# SolenoidDriverCircuit.net
KiCad netlist of a schematic drawn in EAGLE
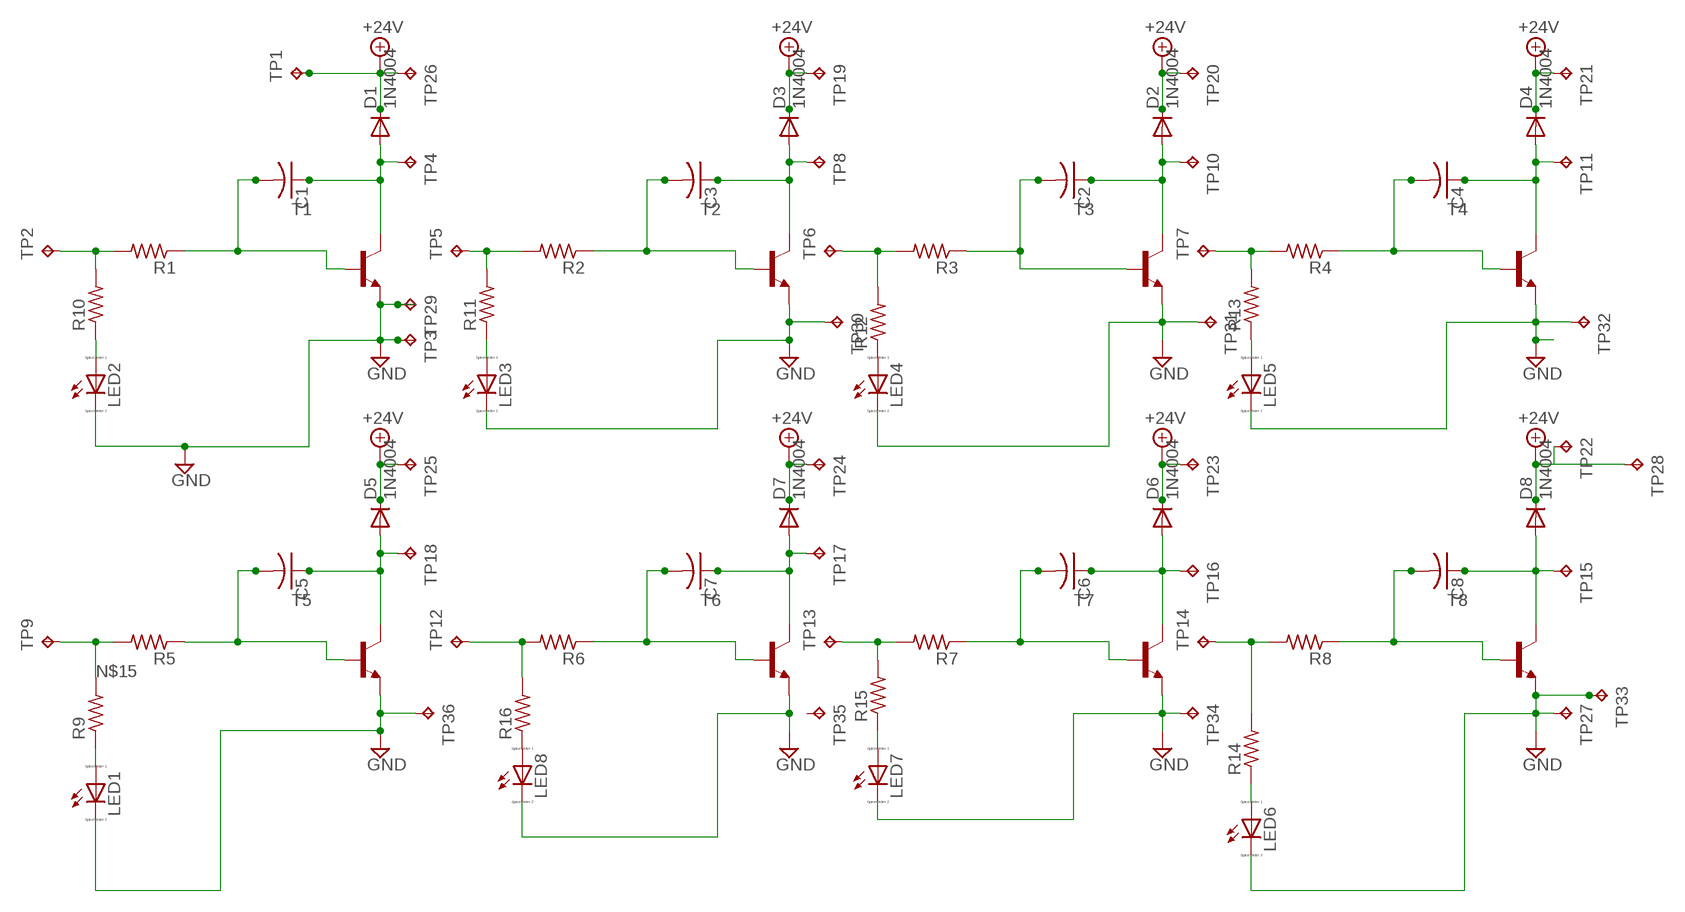
[diagram p0: schematic, sheet 1]

(export (version "E")
  (design (tool "Eeschema 10.0.6"))
  (components
    (comp (ref "C1")
      (value "C-US050-024X044")
      (footprint "eagle-import:C050-024X044")
      (libsource (lib "eagle-import") (part "C-US050-024X044"))
    )
    (comp (ref "C2")
      (value "C-US050-024X044")
      (footprint "eagle-import:C050-024X044")
      (libsource (lib "eagle-import") (part "C-US050-024X044"))
    )
    (comp (ref "C3")
      (value "C-US050-024X044")
      (footprint "eagle-import:C050-024X044")
      (libsource (lib "eagle-import") (part "C-US050-024X044"))
    )
    (comp (ref "C4")
      (value "C-US050-024X044")
      (footprint "eagle-import:C050-024X044")
      (libsource (lib "eagle-import") (part "C-US050-024X044"))
    )
    (comp (ref "C5")
      (value "C-US050-024X044")
      (footprint "eagle-import:C050-024X044")
      (libsource (lib "eagle-import") (part "C-US050-024X044"))
    )
    (comp (ref "C6")
      (value "C-US050-024X044")
      (footprint "eagle-import:C050-024X044")
      (libsource (lib "eagle-import") (part "C-US050-024X044"))
    )
    (comp (ref "C7")
      (value "C-US050-024X044")
      (footprint "eagle-import:C050-024X044")
      (libsource (lib "eagle-import") (part "C-US050-024X044"))
    )
    (comp (ref "C8")
      (value "C-US050-024X044")
      (footprint "eagle-import:C050-024X044")
      (libsource (lib "eagle-import") (part "C-US050-024X044"))
    )
    (comp (ref "D1")
      (value "1N4004")
      (footprint "eagle-import:DO41-10")
      (libsource (lib "eagle-import") (part "1N4004"))
    )
    (comp (ref "D2")
      (value "1N4004")
      (footprint "eagle-import:DO41-10")
      (libsource (lib "eagle-import") (part "1N4004"))
    )
    (comp (ref "D3")
      (value "1N4004")
      (footprint "eagle-import:DO41-10")
      (libsource (lib "eagle-import") (part "1N4004"))
    )
    (comp (ref "D4")
      (value "1N4004")
      (footprint "eagle-import:DO41-10")
      (libsource (lib "eagle-import") (part "1N4004"))
    )
    (comp (ref "D5")
      (value "1N4004")
      (footprint "eagle-import:DO41-10")
      (libsource (lib "eagle-import") (part "1N4004"))
    )
    (comp (ref "D6")
      (value "1N4004")
      (footprint "eagle-import:DO41-10")
      (libsource (lib "eagle-import") (part "1N4004"))
    )
    (comp (ref "D7")
      (value "1N4004")
      (footprint "eagle-import:DO41-10")
      (libsource (lib "eagle-import") (part "1N4004"))
    )
    (comp (ref "D8")
      (value "1N4004")
      (footprint "eagle-import:DO41-10")
      (libsource (lib "eagle-import") (part "1N4004"))
    )
    (comp (ref "LED1")
      (value "LED_ELD260")
      (footprint "eagle-import:LED_LD260")
      (libsource (lib "eagle-import") (part "LED_ELD260"))
    )
    (comp (ref "LED2")
      (value "LED_ELD260")
      (footprint "eagle-import:LED_LD260")
      (libsource (lib "eagle-import") (part "LED_ELD260"))
    )
    (comp (ref "LED3")
      (value "LED_ELD260")
      (footprint "eagle-import:LED_LD260")
      (libsource (lib "eagle-import") (part "LED_ELD260"))
    )
    (comp (ref "LED4")
      (value "LED_ELD260")
      (footprint "eagle-import:LED_LD260")
      (libsource (lib "eagle-import") (part "LED_ELD260"))
    )
    (comp (ref "LED5")
      (value "LED_ELD260")
      (footprint "eagle-import:LED_LD260")
      (libsource (lib "eagle-import") (part "LED_ELD260"))
    )
    (comp (ref "LED6")
      (value "LED_ELD260")
      (footprint "eagle-import:LED_LD260")
      (libsource (lib "eagle-import") (part "LED_ELD260"))
    )
    (comp (ref "LED7")
      (value "LED_ELD260")
      (footprint "eagle-import:LED_LD260")
      (libsource (lib "eagle-import") (part "LED_ELD260"))
    )
    (comp (ref "LED8")
      (value "LED_ELD260")
      (footprint "eagle-import:LED_LD260")
      (libsource (lib "eagle-import") (part "LED_ELD260"))
    )
    (comp (ref "R1")
      (value "R-US_0207/2V")
      (footprint "eagle-import:0207_2V")
      (libsource (lib "eagle-import") (part "R-US_0207/2V"))
    )
    (comp (ref "R2")
      (value "R-US_0207/2V")
      (footprint "eagle-import:0207_2V")
      (libsource (lib "eagle-import") (part "R-US_0207/2V"))
    )
    (comp (ref "R3")
      (value "R-US_0207/2V")
      (footprint "eagle-import:0207_2V")
      (libsource (lib "eagle-import") (part "R-US_0207/2V"))
    )
    (comp (ref "R4")
      (value "R-US_0207/2V")
      (footprint "eagle-import:0207_2V")
      (libsource (lib "eagle-import") (part "R-US_0207/2V"))
    )
    (comp (ref "R5")
      (value "R-US_0207/2V")
      (footprint "eagle-import:0207_2V")
      (libsource (lib "eagle-import") (part "R-US_0207/2V"))
    )
    (comp (ref "R6")
      (value "R-US_0207/2V")
      (footprint "eagle-import:0207_2V")
      (libsource (lib "eagle-import") (part "R-US_0207/2V"))
    )
    (comp (ref "R7")
      (value "R-US_0207/2V")
      (footprint "eagle-import:0207_2V")
      (libsource (lib "eagle-import") (part "R-US_0207/2V"))
    )
    (comp (ref "R8")
      (value "R-US_0207/2V")
      (footprint "eagle-import:0207_2V")
      (libsource (lib "eagle-import") (part "R-US_0207/2V"))
    )
    (comp (ref "R9")
      (value "R-US_0207/2V")
      (footprint "eagle-import:0207_2V")
      (libsource (lib "eagle-import") (part "R-US_0207/2V"))
    )
    (comp (ref "R10")
      (value "R-US_0207/2V")
      (footprint "eagle-import:0207_2V")
      (libsource (lib "eagle-import") (part "R-US_0207/2V"))
    )
    (comp (ref "R11")
      (value "R-US_0207/2V")
      (footprint "eagle-import:0207_2V")
      (libsource (lib "eagle-import") (part "R-US_0207/2V"))
    )
    (comp (ref "R12")
      (value "R-US_0207/2V")
      (footprint "eagle-import:0207_2V")
      (libsource (lib "eagle-import") (part "R-US_0207/2V"))
    )
    (comp (ref "R13")
      (value "R-US_0207/2V")
      (footprint "eagle-import:0207_2V")
      (libsource (lib "eagle-import") (part "R-US_0207/2V"))
    )
    (comp (ref "R14")
      (value "R-US_0207/2V")
      (footprint "eagle-import:0207_2V")
      (libsource (lib "eagle-import") (part "R-US_0207/2V"))
    )
    (comp (ref "R15")
      (value "R-US_0207/2V")
      (footprint "eagle-import:0207_2V")
      (libsource (lib "eagle-import") (part "R-US_0207/2V"))
    )
    (comp (ref "R16")
      (value "R-US_0207/2V")
      (footprint "eagle-import:0207_2V")
      (libsource (lib "eagle-import") (part "R-US_0207/2V"))
    )
    (comp (ref "T1")
      (value "-NPN-TO220V")
      (footprint "eagle-import:TO220V")
      (libsource (lib "eagle-import") (part "-NPN-TO220V"))
    )
    (comp (ref "T2")
      (value "-NPN-TO220V")
      (footprint "eagle-import:TO220V")
      (libsource (lib "eagle-import") (part "-NPN-TO220V"))
    )
    (comp (ref "T3")
      (value "-NPN-TO220V")
      (footprint "eagle-import:TO220V")
      (libsource (lib "eagle-import") (part "-NPN-TO220V"))
    )
    (comp (ref "T4")
      (value "-NPN-TO220V")
      (footprint "eagle-import:TO220V")
      (libsource (lib "eagle-import") (part "-NPN-TO220V"))
    )
    (comp (ref "T5")
      (value "-NPN-TO220V")
      (footprint "eagle-import:TO220V")
      (libsource (lib "eagle-import") (part "-NPN-TO220V"))
    )
    (comp (ref "T6")
      (value "-NPN-TO220V")
      (footprint "eagle-import:TO220V")
      (libsource (lib "eagle-import") (part "-NPN-TO220V"))
    )
    (comp (ref "T7")
      (value "-NPN-TO220V")
      (footprint "eagle-import:TO220V")
      (libsource (lib "eagle-import") (part "-NPN-TO220V"))
    )
    (comp (ref "T8")
      (value "-NPN-TO220V")
      (footprint "eagle-import:TO220V")
      (libsource (lib "eagle-import") (part "-NPN-TO220V"))
    )
    (comp (ref "TP1")
      (value "TPPAD1-13Y")
      (footprint "eagle-import:P1-13Y")
      (libsource (lib "eagle-import") (part "TPPAD1-13Y"))
    )
    (comp (ref "TP2")
      (value "TPPAD1-13")
      (footprint "eagle-import:P1-13")
      (libsource (lib "eagle-import") (part "TPPAD1-13"))
    )
    (comp (ref "TP3")
      (value "TPPAD1-13Y")
      (footprint "eagle-import:P1-13Y")
      (libsource (lib "eagle-import") (part "TPPAD1-13Y"))
    )
    (comp (ref "TP4")
      (value "TPPAD1-13Y")
      (footprint "eagle-import:P1-13Y")
      (libsource (lib "eagle-import") (part "TPPAD1-13Y"))
    )
    (comp (ref "TP5")
      (value "TPPAD1-13")
      (footprint "eagle-import:P1-13")
      (libsource (lib "eagle-import") (part "TPPAD1-13"))
    )
    (comp (ref "TP6")
      (value "TPPAD1-13")
      (footprint "eagle-import:P1-13")
      (libsource (lib "eagle-import") (part "TPPAD1-13"))
    )
    (comp (ref "TP7")
      (value "TPPAD1-13")
      (footprint "eagle-import:P1-13")
      (libsource (lib "eagle-import") (part "TPPAD1-13"))
    )
    (comp (ref "TP8")
      (value "TPPAD1-13Y")
      (footprint "eagle-import:P1-13Y")
      (libsource (lib "eagle-import") (part "TPPAD1-13Y"))
    )
    (comp (ref "TP9")
      (value "TPPAD1-13")
      (footprint "eagle-import:P1-13")
      (libsource (lib "eagle-import") (part "TPPAD1-13"))
    )
    (comp (ref "TP10")
      (value "TPPAD1-13Y")
      (footprint "eagle-import:P1-13Y")
      (libsource (lib "eagle-import") (part "TPPAD1-13Y"))
    )
    (comp (ref "TP11")
      (value "TPPAD1-13Y")
      (footprint "eagle-import:P1-13Y")
      (libsource (lib "eagle-import") (part "TPPAD1-13Y"))
    )
    (comp (ref "TP12")
      (value "TPPAD1-13")
      (footprint "eagle-import:P1-13")
      (libsource (lib "eagle-import") (part "TPPAD1-13"))
    )
    (comp (ref "TP13")
      (value "TPPAD1-13")
      (footprint "eagle-import:P1-13")
      (libsource (lib "eagle-import") (part "TPPAD1-13"))
    )
    (comp (ref "TP14")
      (value "TPPAD1-13")
      (footprint "eagle-import:P1-13")
      (libsource (lib "eagle-import") (part "TPPAD1-13"))
    )
    (comp (ref "TP15")
      (value "TPPAD1-13Y")
      (footprint "eagle-import:P1-13Y")
      (libsource (lib "eagle-import") (part "TPPAD1-13Y"))
    )
    (comp (ref "TP16")
      (value "TPPAD1-13Y")
      (footprint "eagle-import:P1-13Y")
      (libsource (lib "eagle-import") (part "TPPAD1-13Y"))
    )
    (comp (ref "TP17")
      (value "TPPAD1-13Y")
      (footprint "eagle-import:P1-13Y")
      (libsource (lib "eagle-import") (part "TPPAD1-13Y"))
    )
    (comp (ref "TP18")
      (value "TPPAD1-13Y")
      (footprint "eagle-import:P1-13Y")
      (libsource (lib "eagle-import") (part "TPPAD1-13Y"))
    )
    (comp (ref "TP19")
      (value "TPPAD1-13Y")
      (footprint "eagle-import:P1-13Y")
      (libsource (lib "eagle-import") (part "TPPAD1-13Y"))
    )
    (comp (ref "TP20")
      (value "TPPAD1-13Y")
      (footprint "eagle-import:P1-13Y")
      (libsource (lib "eagle-import") (part "TPPAD1-13Y"))
    )
    (comp (ref "TP21")
      (value "TPPAD1-13Y")
      (footprint "eagle-import:P1-13Y")
      (libsource (lib "eagle-import") (part "TPPAD1-13Y"))
    )
    (comp (ref "TP22")
      (value "TPPAD1-13Y")
      (footprint "eagle-import:P1-13Y")
      (libsource (lib "eagle-import") (part "TPPAD1-13Y"))
    )
    (comp (ref "TP23")
      (value "TPPAD1-13Y")
      (footprint "eagle-import:P1-13Y")
      (libsource (lib "eagle-import") (part "TPPAD1-13Y"))
    )
    (comp (ref "TP24")
      (value "TPPAD1-13Y")
      (footprint "eagle-import:P1-13Y")
      (libsource (lib "eagle-import") (part "TPPAD1-13Y"))
    )
    (comp (ref "TP25")
      (value "TPPAD1-13Y")
      (footprint "eagle-import:P1-13Y")
      (libsource (lib "eagle-import") (part "TPPAD1-13Y"))
    )
    (comp (ref "TP26")
      (value "TPPAD1-13Y")
      (footprint "eagle-import:P1-13Y")
      (libsource (lib "eagle-import") (part "TPPAD1-13Y"))
    )
    (comp (ref "TP27")
      (value "TPPAD1-13Y")
      (footprint "eagle-import:P1-13Y")
      (libsource (lib "eagle-import") (part "TPPAD1-13Y"))
    )
    (comp (ref "TP28")
      (value "TPPAD1-13Y")
      (footprint "eagle-import:P1-13Y")
      (libsource (lib "eagle-import") (part "TPPAD1-13Y"))
    )
    (comp (ref "TP29")
      (value "TPPAD1-13")
      (footprint "eagle-import:P1-13")
      (libsource (lib "eagle-import") (part "TPPAD1-13"))
    )
    (comp (ref "TP30")
      (value "TPPAD1-13")
      (footprint "eagle-import:P1-13")
      (libsource (lib "eagle-import") (part "TPPAD1-13"))
    )
    (comp (ref "TP31")
      (value "TPPAD1-13")
      (footprint "eagle-import:P1-13")
      (libsource (lib "eagle-import") (part "TPPAD1-13"))
    )
    (comp (ref "TP32")
      (value "TPPAD1-13")
      (footprint "eagle-import:P1-13")
      (libsource (lib "eagle-import") (part "TPPAD1-13"))
    )
    (comp (ref "TP33")
      (value "TPPAD1-13")
      (footprint "eagle-import:P1-13")
      (libsource (lib "eagle-import") (part "TPPAD1-13"))
    )
    (comp (ref "TP34")
      (value "TPPAD1-13")
      (footprint "eagle-import:P1-13")
      (libsource (lib "eagle-import") (part "TPPAD1-13"))
    )
    (comp (ref "TP35")
      (value "TPPAD1-13")
      (footprint "eagle-import:P1-13")
      (libsource (lib "eagle-import") (part "TPPAD1-13"))
    )
    (comp (ref "TP36")
      (value "TPPAD1-13")
      (footprint "eagle-import:P1-13")
      (libsource (lib "eagle-import") (part "TPPAD1-13"))
    )
  )
  (nets
    (net (code "1") (name "+24V") (class "Default")
      (node (ref "D1") (pin "C") (pinfunction "C_C") (pintype "passive"))
      (node (ref "D2") (pin "C") (pinfunction "C_C") (pintype "passive"))
      (node (ref "D3") (pin "C") (pinfunction "C_C") (pintype "passive"))
      (node (ref "D4") (pin "C") (pinfunction "C_C") (pintype "passive"))
      (node (ref "D5") (pin "C") (pinfunction "C_C") (pintype "passive"))
      (node (ref "D6") (pin "C") (pinfunction "C_C") (pintype "passive"))
      (node (ref "D7") (pin "C") (pinfunction "C_C") (pintype "passive"))
      (node (ref "D8") (pin "C") (pinfunction "C_C") (pintype "passive"))
      (node (ref "TP1") (pin "TP") (pinfunction "TP_TP") (pintype "input"))
      (node (ref "TP19") (pin "TP") (pinfunction "TP_TP") (pintype "input"))
      (node (ref "TP20") (pin "TP") (pinfunction "TP_TP") (pintype "input"))
      (node (ref "TP21") (pin "TP") (pinfunction "TP_TP") (pintype "input"))
      (node (ref "TP22") (pin "TP") (pinfunction "TP_TP") (pintype "input"))
      (node (ref "TP23") (pin "TP") (pinfunction "TP_TP") (pintype "input"))
      (node (ref "TP24") (pin "TP") (pinfunction "TP_TP") (pintype "input"))
      (node (ref "TP25") (pin "TP") (pinfunction "TP_TP") (pintype "input"))
      (node (ref "TP26") (pin "TP") (pinfunction "TP_TP") (pintype "input"))
      (node (ref "TP28") (pin "TP") (pinfunction "TP_TP") (pintype "input"))
    )
    (net (code "2") (name "/N$15") (class "Default")
      (node (ref "R5") (pin "2") (pinfunction "2_2") (pintype "passive"))
      (node (ref "R9") (pin "2") (pinfunction "2_2") (pintype "passive"))
      (node (ref "TP9") (pin "TP") (pinfunction "TP_TP") (pintype "input"))
    )
    (net (code "3") (name "GND") (class "Default")
      (node (ref "LED1") (pin "K") (pinfunction "C_K") (pintype "passive"))
      (node (ref "LED2") (pin "K") (pinfunction "C_K") (pintype "passive"))
      (node (ref "LED3") (pin "K") (pinfunction "C_K") (pintype "passive"))
      (node (ref "LED4") (pin "K") (pinfunction "C_K") (pintype "passive"))
      (node (ref "LED5") (pin "K") (pinfunction "C_K") (pintype "passive"))
      (node (ref "LED6") (pin "K") (pinfunction "C_K") (pintype "passive"))
      (node (ref "LED7") (pin "K") (pinfunction "C_K") (pintype "passive"))
      (node (ref "LED8") (pin "K") (pinfunction "C_K") (pintype "passive"))
      (node (ref "T1") (pin "3") (pinfunction "E_3") (pintype "passive"))
      (node (ref "T2") (pin "3") (pinfunction "E_3") (pintype "passive"))
      (node (ref "T3") (pin "3") (pinfunction "E_3") (pintype "passive"))
      (node (ref "T4") (pin "3") (pinfunction "E_3") (pintype "passive"))
      (node (ref "T5") (pin "3") (pinfunction "E_3") (pintype "passive"))
      (node (ref "T6") (pin "3") (pinfunction "E_3") (pintype "passive"))
      (node (ref "T7") (pin "3") (pinfunction "E_3") (pintype "passive"))
      (node (ref "T8") (pin "3") (pinfunction "E_3") (pintype "passive"))
      (node (ref "TP27") (pin "TP") (pinfunction "TP_TP") (pintype "input"))
      (node (ref "TP29") (pin "TP") (pinfunction "TP_TP") (pintype "input"))
      (node (ref "TP3") (pin "TP") (pinfunction "TP_TP") (pintype "input"))
      (node (ref "TP30") (pin "TP") (pinfunction "TP_TP") (pintype "input"))
      (node (ref "TP31") (pin "TP") (pinfunction "TP_TP") (pintype "input"))
      (node (ref "TP32") (pin "TP") (pinfunction "TP_TP") (pintype "input"))
      (node (ref "TP33") (pin "TP") (pinfunction "TP_TP") (pintype "input"))
      (node (ref "TP34") (pin "TP") (pinfunction "TP_TP") (pintype "input"))
      (node (ref "TP36") (pin "TP") (pinfunction "TP_TP") (pintype "input"))
    )
    (net (code "4") (name "Net-(LED1-PadA)") (class "Default")
      (node (ref "LED1") (pin "A") (pinfunction "A_A") (pintype "passive"))
      (node (ref "R9") (pin "1") (pinfunction "1_1") (pintype "passive"))
    )
    (net (code "5") (name "Net-(LED2-PadA)") (class "Default")
      (node (ref "LED2") (pin "A") (pinfunction "A_A") (pintype "passive"))
      (node (ref "R10") (pin "1") (pinfunction "1_1") (pintype "passive"))
    )
    (net (code "6") (name "Net-(LED3-PadA)") (class "Default")
      (node (ref "LED3") (pin "A") (pinfunction "A_A") (pintype "passive"))
      (node (ref "R11") (pin "1") (pinfunction "1_1") (pintype "passive"))
    )
    (net (code "7") (name "Net-(LED4-PadA)") (class "Default")
      (node (ref "LED4") (pin "A") (pinfunction "A_A") (pintype "passive"))
      (node (ref "R12") (pin "1") (pinfunction "1_1") (pintype "passive"))
    )
    (net (code "8") (name "Net-(LED5-PadA)") (class "Default")
      (node (ref "LED5") (pin "A") (pinfunction "A_A") (pintype "passive"))
      (node (ref "R13") (pin "1") (pinfunction "1_1") (pintype "passive"))
    )
    (net (code "9") (name "Net-(LED6-PadA)") (class "Default")
      (node (ref "LED6") (pin "A") (pinfunction "A_A") (pintype "passive"))
      (node (ref "R14") (pin "1") (pinfunction "1_1") (pintype "passive"))
    )
    (net (code "10") (name "Net-(LED7-PadA)") (class "Default")
      (node (ref "LED7") (pin "A") (pinfunction "A_A") (pintype "passive"))
      (node (ref "R15") (pin "1") (pinfunction "1_1") (pintype "passive"))
    )
    (net (code "11") (name "Net-(LED8-PadA)") (class "Default")
      (node (ref "LED8") (pin "A") (pinfunction "A_A") (pintype "passive"))
      (node (ref "R16") (pin "1") (pinfunction "1_1") (pintype "passive"))
    )
    (net (code "12") (name "Net-(R1-Pad2)") (class "Default")
      (node (ref "R1") (pin "2") (pinfunction "2_2") (pintype "passive"))
      (node (ref "R10") (pin "2") (pinfunction "2_2") (pintype "passive"))
      (node (ref "TP2") (pin "TP") (pinfunction "TP_TP") (pintype "input"))
    )
    (net (code "13") (name "Net-(R11-Pad2)") (class "Default")
      (node (ref "R11") (pin "2") (pinfunction "2_2") (pintype "passive"))
      (node (ref "R2") (pin "2") (pinfunction "2_2") (pintype "passive"))
      (node (ref "TP5") (pin "TP") (pinfunction "TP_TP") (pintype "input"))
    )
    (net (code "14") (name "Net-(R12-Pad2)") (class "Default")
      (node (ref "R12") (pin "2") (pinfunction "2_2") (pintype "passive"))
      (node (ref "R3") (pin "2") (pinfunction "2_2") (pintype "passive"))
      (node (ref "TP6") (pin "TP") (pinfunction "TP_TP") (pintype "input"))
    )
    (net (code "15") (name "Net-(R13-Pad2)") (class "Default")
      (node (ref "R13") (pin "2") (pinfunction "2_2") (pintype "passive"))
      (node (ref "R4") (pin "2") (pinfunction "2_2") (pintype "passive"))
      (node (ref "TP7") (pin "TP") (pinfunction "TP_TP") (pintype "input"))
    )
    (net (code "16") (name "Net-(R14-Pad2)") (class "Default")
      (node (ref "R14") (pin "2") (pinfunction "2_2") (pintype "passive"))
      (node (ref "R8") (pin "2") (pinfunction "2_2") (pintype "passive"))
      (node (ref "TP14") (pin "TP") (pinfunction "TP_TP") (pintype "input"))
    )
    (net (code "17") (name "Net-(R15-Pad2)") (class "Default")
      (node (ref "R15") (pin "2") (pinfunction "2_2") (pintype "passive"))
      (node (ref "R7") (pin "2") (pinfunction "2_2") (pintype "passive"))
      (node (ref "TP13") (pin "TP") (pinfunction "TP_TP") (pintype "input"))
    )
    (net (code "18") (name "Net-(R16-Pad2)") (class "Default")
      (node (ref "R16") (pin "2") (pinfunction "2_2") (pintype "passive"))
      (node (ref "R6") (pin "2") (pinfunction "2_2") (pintype "passive"))
      (node (ref "TP12") (pin "TP") (pinfunction "TP_TP") (pintype "input"))
    )
    (net (code "19") (name "Net-(T1-B)") (class "Default")
      (node (ref "C1") (pin "2") (pinfunction "2_2") (pintype "passive"))
      (node (ref "R1") (pin "1") (pinfunction "1_1") (pintype "passive"))
      (node (ref "T1") (pin "1") (pinfunction "B_1") (pintype "passive"))
    )
    (net (code "20") (name "Net-(T1-C)") (class "Default")
      (node (ref "C1") (pin "1") (pinfunction "1_1") (pintype "passive"))
      (node (ref "D1") (pin "A") (pinfunction "A_A") (pintype "passive"))
      (node (ref "T1") (pin "2") (pinfunction "C_2") (pintype "passive"))
      (node (ref "TP4") (pin "TP") (pinfunction "TP_TP") (pintype "input"))
    )
    (net (code "21") (name "Net-(T2-B)") (class "Default")
      (node (ref "C3") (pin "2") (pinfunction "2_2") (pintype "passive"))
      (node (ref "R2") (pin "1") (pinfunction "1_1") (pintype "passive"))
      (node (ref "T2") (pin "1") (pinfunction "B_1") (pintype "passive"))
    )
    (net (code "22") (name "Net-(T2-C)") (class "Default")
      (node (ref "C3") (pin "1") (pinfunction "1_1") (pintype "passive"))
      (node (ref "D3") (pin "A") (pinfunction "A_A") (pintype "passive"))
      (node (ref "T2") (pin "2") (pinfunction "C_2") (pintype "passive"))
      (node (ref "TP8") (pin "TP") (pinfunction "TP_TP") (pintype "input"))
    )
    (net (code "23") (name "Net-(T3-B)") (class "Default")
      (node (ref "C2") (pin "2") (pinfunction "2_2") (pintype "passive"))
      (node (ref "R3") (pin "1") (pinfunction "1_1") (pintype "passive"))
      (node (ref "T3") (pin "1") (pinfunction "B_1") (pintype "passive"))
    )
    (net (code "24") (name "Net-(T3-C)") (class "Default")
      (node (ref "C2") (pin "1") (pinfunction "1_1") (pintype "passive"))
      (node (ref "D2") (pin "A") (pinfunction "A_A") (pintype "passive"))
      (node (ref "T3") (pin "2") (pinfunction "C_2") (pintype "passive"))
      (node (ref "TP10") (pin "TP") (pinfunction "TP_TP") (pintype "input"))
    )
    (net (code "25") (name "Net-(T4-B)") (class "Default")
      (node (ref "C4") (pin "2") (pinfunction "2_2") (pintype "passive"))
      (node (ref "R4") (pin "1") (pinfunction "1_1") (pintype "passive"))
      (node (ref "T4") (pin "1") (pinfunction "B_1") (pintype "passive"))
    )
    (net (code "26") (name "Net-(T4-C)") (class "Default")
      (node (ref "C4") (pin "1") (pinfunction "1_1") (pintype "passive"))
      (node (ref "D4") (pin "A") (pinfunction "A_A") (pintype "passive"))
      (node (ref "T4") (pin "2") (pinfunction "C_2") (pintype "passive"))
      (node (ref "TP11") (pin "TP") (pinfunction "TP_TP") (pintype "input"))
    )
    (net (code "27") (name "Net-(T5-B)") (class "Default")
      (node (ref "C5") (pin "2") (pinfunction "2_2") (pintype "passive"))
      (node (ref "R5") (pin "1") (pinfunction "1_1") (pintype "passive"))
      (node (ref "T5") (pin "1") (pinfunction "B_1") (pintype "passive"))
    )
    (net (code "28") (name "Net-(T5-C)") (class "Default")
      (node (ref "C5") (pin "1") (pinfunction "1_1") (pintype "passive"))
      (node (ref "D5") (pin "A") (pinfunction "A_A") (pintype "passive"))
      (node (ref "T5") (pin "2") (pinfunction "C_2") (pintype "passive"))
      (node (ref "TP18") (pin "TP") (pinfunction "TP_TP") (pintype "input"))
    )
    (net (code "29") (name "Net-(T6-B)") (class "Default")
      (node (ref "C7") (pin "2") (pinfunction "2_2") (pintype "passive"))
      (node (ref "R6") (pin "1") (pinfunction "1_1") (pintype "passive"))
      (node (ref "T6") (pin "1") (pinfunction "B_1") (pintype "passive"))
    )
    (net (code "30") (name "Net-(T6-C)") (class "Default")
      (node (ref "C7") (pin "1") (pinfunction "1_1") (pintype "passive"))
      (node (ref "D7") (pin "A") (pinfunction "A_A") (pintype "passive"))
      (node (ref "T6") (pin "2") (pinfunction "C_2") (pintype "passive"))
      (node (ref "TP17") (pin "TP") (pinfunction "TP_TP") (pintype "input"))
    )
    (net (code "31") (name "Net-(T7-B)") (class "Default")
      (node (ref "C6") (pin "2") (pinfunction "2_2") (pintype "passive"))
      (node (ref "R7") (pin "1") (pinfunction "1_1") (pintype "passive"))
      (node (ref "T7") (pin "1") (pinfunction "B_1") (pintype "passive"))
    )
    (net (code "32") (name "Net-(T7-C)") (class "Default")
      (node (ref "C6") (pin "1") (pinfunction "1_1") (pintype "passive"))
      (node (ref "D6") (pin "A") (pinfunction "A_A") (pintype "passive"))
      (node (ref "T7") (pin "2") (pinfunction "C_2") (pintype "passive"))
      (node (ref "TP16") (pin "TP") (pinfunction "TP_TP") (pintype "input"))
    )
    (net (code "33") (name "Net-(T8-B)") (class "Default")
      (node (ref "C8") (pin "2") (pinfunction "2_2") (pintype "passive"))
      (node (ref "R8") (pin "1") (pinfunction "1_1") (pintype "passive"))
      (node (ref "T8") (pin "1") (pinfunction "B_1") (pintype "passive"))
    )
    (net (code "34") (name "Net-(T8-C)") (class "Default")
      (node (ref "C8") (pin "1") (pinfunction "1_1") (pintype "passive"))
      (node (ref "D8") (pin "A") (pinfunction "A_A") (pintype "passive"))
      (node (ref "T8") (pin "2") (pinfunction "C_2") (pintype "passive"))
      (node (ref "TP15") (pin "TP") (pinfunction "TP_TP") (pintype "input"))
    )
    (net (code "35") (name "unconnected-(TP35-PadTP)") (class "Default")
      (node (ref "TP35") (pin "TP") (pinfunction "TP_TP") (pintype "input"))
    )
  )
)
